# Buck_Boost_19V.net
KiCad netlist of a schematic drawn in Altium Designer
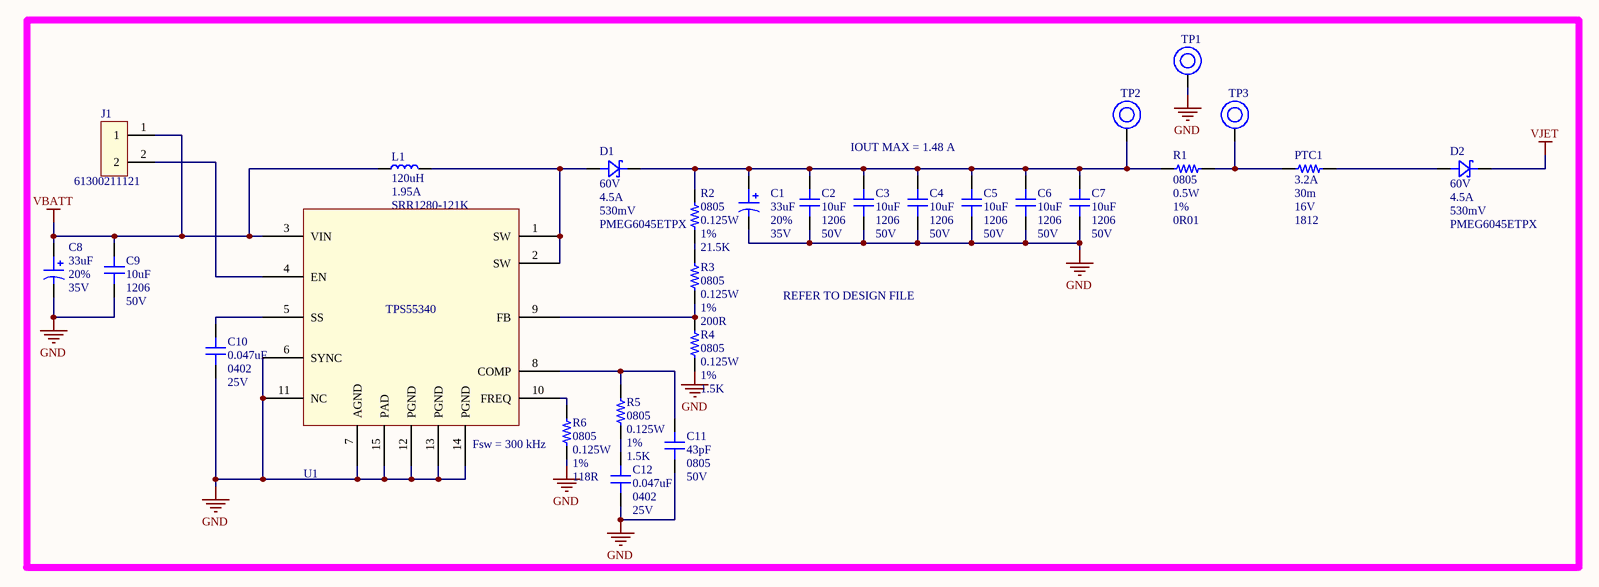
[diagram p0: Buck Boost 19V.SchDoc]

(export (version "E")
  (design (tool "Eeschema 10.0.6"))
  (components
    (comp (ref "C1")
      (value "33uF")
      (footprint "CAP ALU - 6.3mm DIA")
      (description "CAP ALU 33µF 35V")
      (fields
        (field (name "PART NUMBER") "EEE-FK1V330P")
        (field (name "TOLERANCE") "20%")
        (field (name "VOLTAGE") "35V")
        (field (name "Comment") "CAP_EEE-FK1V330P")
      )
      (libsource (lib "SecureBot") (part "CAP_EEE-FK1V330P"))
    )
    (comp (ref "C2")
      (value "10uF")
      (footprint "CAP_1206")
      (description "CAP CER 10uF 50V 1206")
      (fields
        (field (name "PART NUMBER") "GRT31CR61H106ME01L‎")
        (field (name "PACKAGE") "1206")
        (field (name "VOLTAGE") "50V")
        (field (name "Comment") "CAP_GRT31CR61H106ME01L‎")
      )
      (libsource (lib "SecureBot") (part "CAP_GRT31CR61H106ME01L‎"))
    )
    (comp (ref "C3")
      (value "10uF")
      (footprint "CAP_1206")
      (description "CAP CER 10uF 50V 1206")
      (fields
        (field (name "PART NUMBER") "GRT31CR61H106ME01L‎")
        (field (name "PACKAGE") "1206")
        (field (name "VOLTAGE") "50V")
        (field (name "Comment") "CAP_GRT31CR61H106ME01L‎")
      )
      (libsource (lib "SecureBot") (part "CAP_GRT31CR61H106ME01L‎"))
    )
    (comp (ref "C4")
      (value "10uF")
      (footprint "CAP_1206")
      (description "CAP CER 10uF 50V 1206")
      (fields
        (field (name "PART NUMBER") "GRT31CR61H106ME01L‎")
        (field (name "PACKAGE") "1206")
        (field (name "VOLTAGE") "50V")
        (field (name "Comment") "CAP_GRT31CR61H106ME01L‎")
      )
      (libsource (lib "SecureBot") (part "CAP_GRT31CR61H106ME01L‎"))
    )
    (comp (ref "C5")
      (value "10uF")
      (footprint "CAP_1206")
      (description "CAP CER 10uF 50V 1206")
      (fields
        (field (name "PART NUMBER") "GRT31CR61H106ME01L‎")
        (field (name "PACKAGE") "1206")
        (field (name "VOLTAGE") "50V")
        (field (name "Comment") "CAP_GRT31CR61H106ME01L‎")
      )
      (libsource (lib "SecureBot") (part "CAP_GRT31CR61H106ME01L‎"))
    )
    (comp (ref "C6")
      (value "10uF")
      (footprint "CAP_1206")
      (description "CAP CER 10uF 50V 1206")
      (fields
        (field (name "PART NUMBER") "GRT31CR61H106ME01L‎")
        (field (name "PACKAGE") "1206")
        (field (name "VOLTAGE") "50V")
        (field (name "Comment") "CAP_GRT31CR61H106ME01L‎")
      )
      (libsource (lib "SecureBot") (part "CAP_GRT31CR61H106ME01L‎"))
    )
    (comp (ref "C7")
      (value "10uF")
      (footprint "CAP_1206")
      (description "CAP CER 10uF 50V 1206")
      (fields
        (field (name "PART NUMBER") "GRT31CR61H106ME01L‎")
        (field (name "PACKAGE") "1206")
        (field (name "VOLTAGE") "50V")
        (field (name "Comment") "CAP_GRT31CR61H106ME01L‎")
      )
      (libsource (lib "SecureBot") (part "CAP_GRT31CR61H106ME01L‎"))
    )
    (comp (ref "C8")
      (value "33uF")
      (footprint "CAP ALU - 6.3mm DIA")
      (description "CAP ALU 33µF 35V")
      (fields
        (field (name "PART NUMBER") "EEE-FK1V330P")
        (field (name "TOLERANCE") "20%")
        (field (name "VOLTAGE") "35V")
        (field (name "Comment") "CAP_EEE-FK1V330P")
      )
      (libsource (lib "SecureBot") (part "CAP_EEE-FK1V330P"))
    )
    (comp (ref "C9")
      (value "10uF")
      (footprint "CAP_1206")
      (description "CAP CER 10uF 50V 1206")
      (fields
        (field (name "PART NUMBER") "GRT31CR61H106ME01L‎")
        (field (name "PACKAGE") "1206")
        (field (name "VOLTAGE") "50V")
        (field (name "Comment") "CAP_GRT31CR61H106ME01L‎")
      )
      (libsource (lib "SecureBot") (part "CAP_GRT31CR61H106ME01L‎"))
    )
    (comp (ref "C10")
      (value "0.047uF")
      (footprint "CAP_0402")
      (description "CAP CER 0.047uF 25V 0402")
      (fields
        (field (name "PART NUMBER") "‎C0402C473K3RACAUTO‎")
        (field (name "PACKAGE") "0402")
        (field (name "VOLTAGE") "25V")
        (field (name "Comment") "CAP_‎‎‎C0402C473K3RACAUTO‎")
      )
      (libsource (lib "SecureBot") (part "CAP_‎‎‎C0402C473K3RACAUTO‎"))
    )
    (comp (ref "C11")
      (value "43pF")
      (footprint "CAP_0805")
      (description "CAP CER 43pF 50V 0805")
      (fields
        (field (name "PART NUMBER") "C0805C430J5GAC7800")
        (field (name "TOLERANCE") "5%")
        (field (name "PACKAGE") "0805")
        (field (name "VOLTAGE") "50V")
      )
      (libsource (lib "SecureBot") (part "CAP_‎‎‎C0805C430J5GAC7800"))
    )
    (comp (ref "C12")
      (value "0.047uF")
      (footprint "CAP_0402")
      (description "CAP CER 0.047uF 25V 0402")
      (fields
        (field (name "PART NUMBER") "‎C0402C473K3RACAUTO‎")
        (field (name "PACKAGE") "0402")
        (field (name "VOLTAGE") "25V")
        (field (name "Comment") "CAP_‎‎‎C0402C473K3RACAUTO‎")
      )
      (libsource (lib "SecureBot") (part "CAP_‎‎‎C0402C473K3RACAUTO‎"))
    )
    (comp (ref "D1")
      (value "DIODE_SCH_PMEG6045ETPX")
      (footprint "DO-214AC_SOD128")
      (description "Diode Schottky 60V 4.5A Surface Mount CFP5")
      (fields
        (field (name "VOLTAGE") "60V")
        (field (name "CURRENT") "4.5A")
        (field (name "VF") "530mV")
        (field (name "PART NUMBER") "PMEG6045ETPX")
      )
      (libsource (lib "SecureBot") (part "DIODE_SCH_PMEG6045ETPX"))
    )
    (comp (ref "D2")
      (value "DIODE_SCH_PMEG6045ETPX")
      (footprint "DO-214AC_SOD128")
      (description "Diode Schottky 60V 4.5A Surface Mount CFP5")
      (fields
        (field (name "VOLTAGE") "60V")
        (field (name "CURRENT") "4.5A")
        (field (name "VF") "530mV")
        (field (name "PART NUMBER") "PMEG6045ETPX")
      )
      (libsource (lib "SecureBot") (part "DIODE_SCH_PMEG6045ETPX"))
    )
    (comp (ref "J1")
      (value "Header 2 pin SM")
      (footprint "HDR1X2")
      (fields (field (name "PART NUMBER") "61300211121"))
      (libsource (lib "SecureBot") (part "Header 2 pin SM"))
    )
    (comp (ref "L1")
      (value "120uH")
      (footprint "BOURNS 12.5x12.5mm")
      (description "IND 120µH Shielded Wirewound Inductor 1.95A")
      (fields
        (field (name "TOLERANCE") "20%")
        (field (name "CURRENT") "1.95A")
        (field (name "PART NUMBER") "SRR1280-121K")
        (field (name "Comment") "IND_SRR1280-121K")
      )
      (libsource (lib "SecureBot") (part "IND_SRR1280-121K"))
    )
    (comp (ref "PTC1")
      (value "PTC_0ZCG0160BF2C")
      (footprint "PTC - 1812")
      (description "PTC_Polymeric PTC Resettable Fuse 16V 1.6A Ih")
      (fields
        (field (name "PART NUMBER") "0ZCG0160BF2C")
        (field (name "TRIP VALUE") "3.2A")
        (field (name "RES") "30m")
        (field (name "VOLTAGE") "16V")
        (field (name "PACKAGE") "1812")
      )
      (libsource (lib "SecureBot") (part "PTC_0ZCG0160BF2C"))
    )
    (comp (ref "R1")
      (value "0R01")
      (footprint "RES_0805")
      (description "RES 0.01R 1% 1/2W 0805")
      (fields
        (field (name "PART NUMBER") "KRL1220E-M-R010-F-T5")
        (field (name "PACKAGE") "0805")
        (field (name "POWER") "0.5W")
        (field (name "TOLERANCE") "1%")
        (field (name "Comment") "RES_‎‎‎‎‎ KRL1220E-M-R010-F-T5")
      )
      (libsource (lib "SecureBot") (part "RES_‎‎‎‎‎ KRL1220E-M-R010-F-T5"))
    )
    (comp (ref "R2")
      (value "21.5K")
      (footprint "RES_0805")
      (description "RES 21.5K 1% 1/8W 0805")
      (fields
        (field (name "PART NUMBER") "‎ERJ-6ENF2152V")
        (field (name "PACKAGE") "0805")
        (field (name "POWER") "0.125W")
        (field (name "TOLERANCE") "1%")
        (field (name "Comment") "RES_‎ERJ-6ENF2152V")
      )
      (libsource (lib "SecureBot") (part "RES_‎ERJ-6ENF2152V"))
    )
    (comp (ref "R3")
      (value "200R")
      (footprint "RES_0805")
      (description "RES 200R 1% 1/8W 0805")
      (fields
        (field (name "PART NUMBER") "CRCW0805200RFKEA‎")
        (field (name "PACKAGE") "0805")
        (field (name "POWER") "0.125W")
        (field (name "TOLERANCE") "1%")
        (field (name "Comment") "RES_‎‎CRCW0805200RFKEA‎")
      )
      (libsource (lib "SecureBot") (part "RES_‎‎CRCW0805200RFKEA‎"))
    )
    (comp (ref "R4")
      (value "1.5K")
      (footprint "RES_0805")
      (description "RES 1.5K 1% 1/8W 0805")
      (fields
        (field (name "PART NUMBER") "CRCW08051K50FKEAC")
        (field (name "PACKAGE") "0805")
        (field (name "POWER") "0.125W")
        (field (name "TOLERANCE") "1%")
        (field (name "Comment") "RES_‎‎‎‎CRCW08051K50FKEAC")
      )
      (libsource (lib "SecureBot") (part "RES_‎‎‎‎CRCW08051K50FKEAC"))
    )
    (comp (ref "R5")
      (value "1.5K")
      (footprint "RES_0805")
      (description "RES 1.5K 1% 1/8W 0805")
      (fields
        (field (name "PART NUMBER") "CRCW08051K50FKEAC")
        (field (name "PACKAGE") "0805")
        (field (name "POWER") "0.125W")
        (field (name "TOLERANCE") "1%")
        (field (name "Comment") "RES_‎‎‎‎CRCW08051K50FKEAC")
      )
      (libsource (lib "SecureBot") (part "RES_‎‎‎‎CRCW08051K50FKEAC"))
    )
    (comp (ref "R6")
      (value "118R")
      (footprint "RES_0805")
      (description "RES 118R 1% 1/8W 0805")
      (fields
        (field (name "PART NUMBER") "CRCW0805118KFKEA")
        (field (name "PACKAGE") "0805")
        (field (name "POWER") "0.125W")
        (field (name "TOLERANCE") "1%")
        (field (name "Comment") "RES_‎‎‎CRCW0805118KFKEA")
      )
      (libsource (lib "SecureBot") (part "RES_‎‎‎CRCW0805118KFKEA"))
    )
    (comp (ref "TP1")
      (value "TestPoint 3x3mm")
      (footprint "TestPoint 3X3mm")
      (libsource (lib "SecureBot") (part "TestPoint 3x3mm"))
    )
    (comp (ref "TP2")
      (value "TestPoint 3x3mm")
      (footprint "TestPoint 3X3mm")
      (libsource (lib "SecureBot") (part "TestPoint 3x3mm"))
    )
    (comp (ref "TP3")
      (value "TestPoint 3x3mm")
      (footprint "TestPoint 3X3mm")
      (libsource (lib "SecureBot") (part "TestPoint 3x3mm"))
    )
    (comp (ref "U1")
      (value "REG_BOOST_PS55340")
      (footprint "14-TSSOP")
      (fields (field (name "PART NUMBER") "TPS55340"))
      (libsource (lib "SecureBot") (part "REG_BOOST_PS55340"))
    )
  )
  (nets
    (net (code "1") (name "GND") (class "Default")
      (node (ref "C1") (pin "2") (pinfunction "2_2") (pintype "passive"))
      (node (ref "C10") (pin "2") (pinfunction "2_2") (pintype "passive"))
      (node (ref "C11") (pin "2") (pinfunction "2_2") (pintype "passive"))
      (node (ref "C12") (pin "2") (pinfunction "2_2") (pintype "passive"))
      (node (ref "C2") (pin "2") (pinfunction "2_2") (pintype "passive"))
      (node (ref "C3") (pin "2") (pinfunction "2_2") (pintype "passive"))
      (node (ref "C4") (pin "2") (pinfunction "2_2") (pintype "passive"))
      (node (ref "C5") (pin "2") (pinfunction "2_2") (pintype "passive"))
      (node (ref "C6") (pin "2") (pinfunction "2_2") (pintype "passive"))
      (node (ref "C7") (pin "2") (pinfunction "2_2") (pintype "passive"))
      (node (ref "C8") (pin "2") (pinfunction "2_2") (pintype "passive"))
      (node (ref "C9") (pin "2") (pinfunction "2_2") (pintype "passive"))
      (node (ref "R4") (pin "2") (pinfunction "2_2") (pintype "passive"))
      (node (ref "R6") (pin "2") (pinfunction "2_2") (pintype "passive"))
      (node (ref "TP1") (pin "1") (pinfunction "1_1") (pintype "passive"))
      (node (ref "U1") (pin "11") (pinfunction "NC_11") (pintype "passive"))
      (node (ref "U1") (pin "12") (pinfunction "PGND_12") (pintype "passive"))
      (node (ref "U1") (pin "13") (pinfunction "PGND_13") (pintype "passive"))
      (node (ref "U1") (pin "14") (pinfunction "PGND_14") (pintype "passive"))
      (node (ref "U1") (pin "15") (pinfunction "PAD_15") (pintype "passive"))
      (node (ref "U1") (pin "6") (pinfunction "SYNC_6") (pintype "passive"))
      (node (ref "U1") (pin "7") (pinfunction "AGND_7") (pintype "passive"))
    )
    (net (code "2") (name "Net-(C1-Pad1)") (class "Default")
      (node (ref "C1") (pin "1") (pinfunction "1_1") (pintype "passive"))
      (node (ref "C2") (pin "1") (pinfunction "1_1") (pintype "passive"))
      (node (ref "C3") (pin "1") (pinfunction "1_1") (pintype "passive"))
      (node (ref "C4") (pin "1") (pinfunction "1_1") (pintype "passive"))
      (node (ref "C5") (pin "1") (pinfunction "1_1") (pintype "passive"))
      (node (ref "C6") (pin "1") (pinfunction "1_1") (pintype "passive"))
      (node (ref "C7") (pin "1") (pinfunction "1_1") (pintype "passive"))
      (node (ref "D1") (pin "2") (pinfunction "2_2") (pintype "passive"))
      (node (ref "R1") (pin "1") (pinfunction "1_1") (pintype "passive"))
      (node (ref "R2") (pin "1") (pinfunction "1_1") (pintype "passive"))
      (node (ref "TP2") (pin "1") (pinfunction "1_1") (pintype "passive"))
    )
    (net (code "3") (name "Net-(C12-Pad1)") (class "Default")
      (node (ref "C12") (pin "1") (pinfunction "1_1") (pintype "passive"))
      (node (ref "R5") (pin "2") (pinfunction "2_2") (pintype "passive"))
    )
    (net (code "4") (name "Net-(D1-Pad1)") (class "Default")
      (node (ref "D1") (pin "1") (pinfunction "1_1") (pintype "passive"))
      (node (ref "L1") (pin "2") (pinfunction "2_2") (pintype "passive"))
      (node (ref "U1") (pin "1") (pinfunction "SW_1") (pintype "passive"))
      (node (ref "U1") (pin "2") (pinfunction "SW_2") (pintype "passive"))
    )
    (net (code "5") (name "Net-(D2-Pad1)") (class "Default")
      (node (ref "D2") (pin "1") (pinfunction "1_1") (pintype "passive"))
      (node (ref "PTC1") (pin "2") (pinfunction "2_2") (pintype "passive"))
    )
    (net (code "6") (name "Net-(PTC1-Pad1)") (class "Default")
      (node (ref "PTC1") (pin "1") (pinfunction "1_1") (pintype "passive"))
      (node (ref "R1") (pin "2") (pinfunction "2_2") (pintype "passive"))
      (node (ref "TP3") (pin "1") (pinfunction "1_1") (pintype "passive"))
    )
    (net (code "7") (name "Net-(R2-Pad2)") (class "Default")
      (node (ref "R2") (pin "2") (pinfunction "2_2") (pintype "passive"))
      (node (ref "R3") (pin "1") (pinfunction "1_1") (pintype "passive"))
    )
    (net (code "8") (name "Net-(U1-COMP)") (class "Default")
      (node (ref "C11") (pin "1") (pinfunction "1_1") (pintype "passive"))
      (node (ref "R5") (pin "1") (pinfunction "1_1") (pintype "passive"))
      (node (ref "U1") (pin "8") (pinfunction "COMP_8") (pintype "passive"))
    )
    (net (code "9") (name "Net-(U1-EN)") (class "Default")
      (node (ref "J1") (pin "2") (pinfunction "2_2") (pintype "passive"))
      (node (ref "U1") (pin "4") (pinfunction "EN_4") (pintype "passive"))
    )
    (net (code "10") (name "Net-(U1-FB)") (class "Default")
      (node (ref "R3") (pin "2") (pinfunction "2_2") (pintype "passive"))
      (node (ref "R4") (pin "1") (pinfunction "1_1") (pintype "passive"))
      (node (ref "U1") (pin "9") (pinfunction "FB_9") (pintype "passive"))
    )
    (net (code "11") (name "Net-(U1-FREQ)") (class "Default")
      (node (ref "R6") (pin "1") (pinfunction "1_1") (pintype "passive"))
      (node (ref "U1") (pin "10") (pinfunction "FREQ_10") (pintype "passive"))
    )
    (net (code "12") (name "Net-(U1-SS)") (class "Default")
      (node (ref "C10") (pin "1") (pinfunction "1_1") (pintype "passive"))
      (node (ref "U1") (pin "5") (pinfunction "SS_5") (pintype "passive"))
    )
    (net (code "13") (name "VBATT") (class "Default")
      (node (ref "C8") (pin "1") (pinfunction "1_1") (pintype "passive"))
      (node (ref "C9") (pin "1") (pinfunction "1_1") (pintype "passive"))
      (node (ref "J1") (pin "1") (pinfunction "1_1") (pintype "passive"))
      (node (ref "L1") (pin "1") (pinfunction "1_1") (pintype "passive"))
      (node (ref "U1") (pin "3") (pinfunction "VIN_3") (pintype "passive"))
    )
    (net (code "14") (name "VJET") (class "Default")
      (node (ref "D2") (pin "2") (pinfunction "2_2") (pintype "passive"))
    )
  )
)
